# REUN_468349_001_PSU_Board_Button.net
KiCad netlist of a schematic drawn in Altium Designer
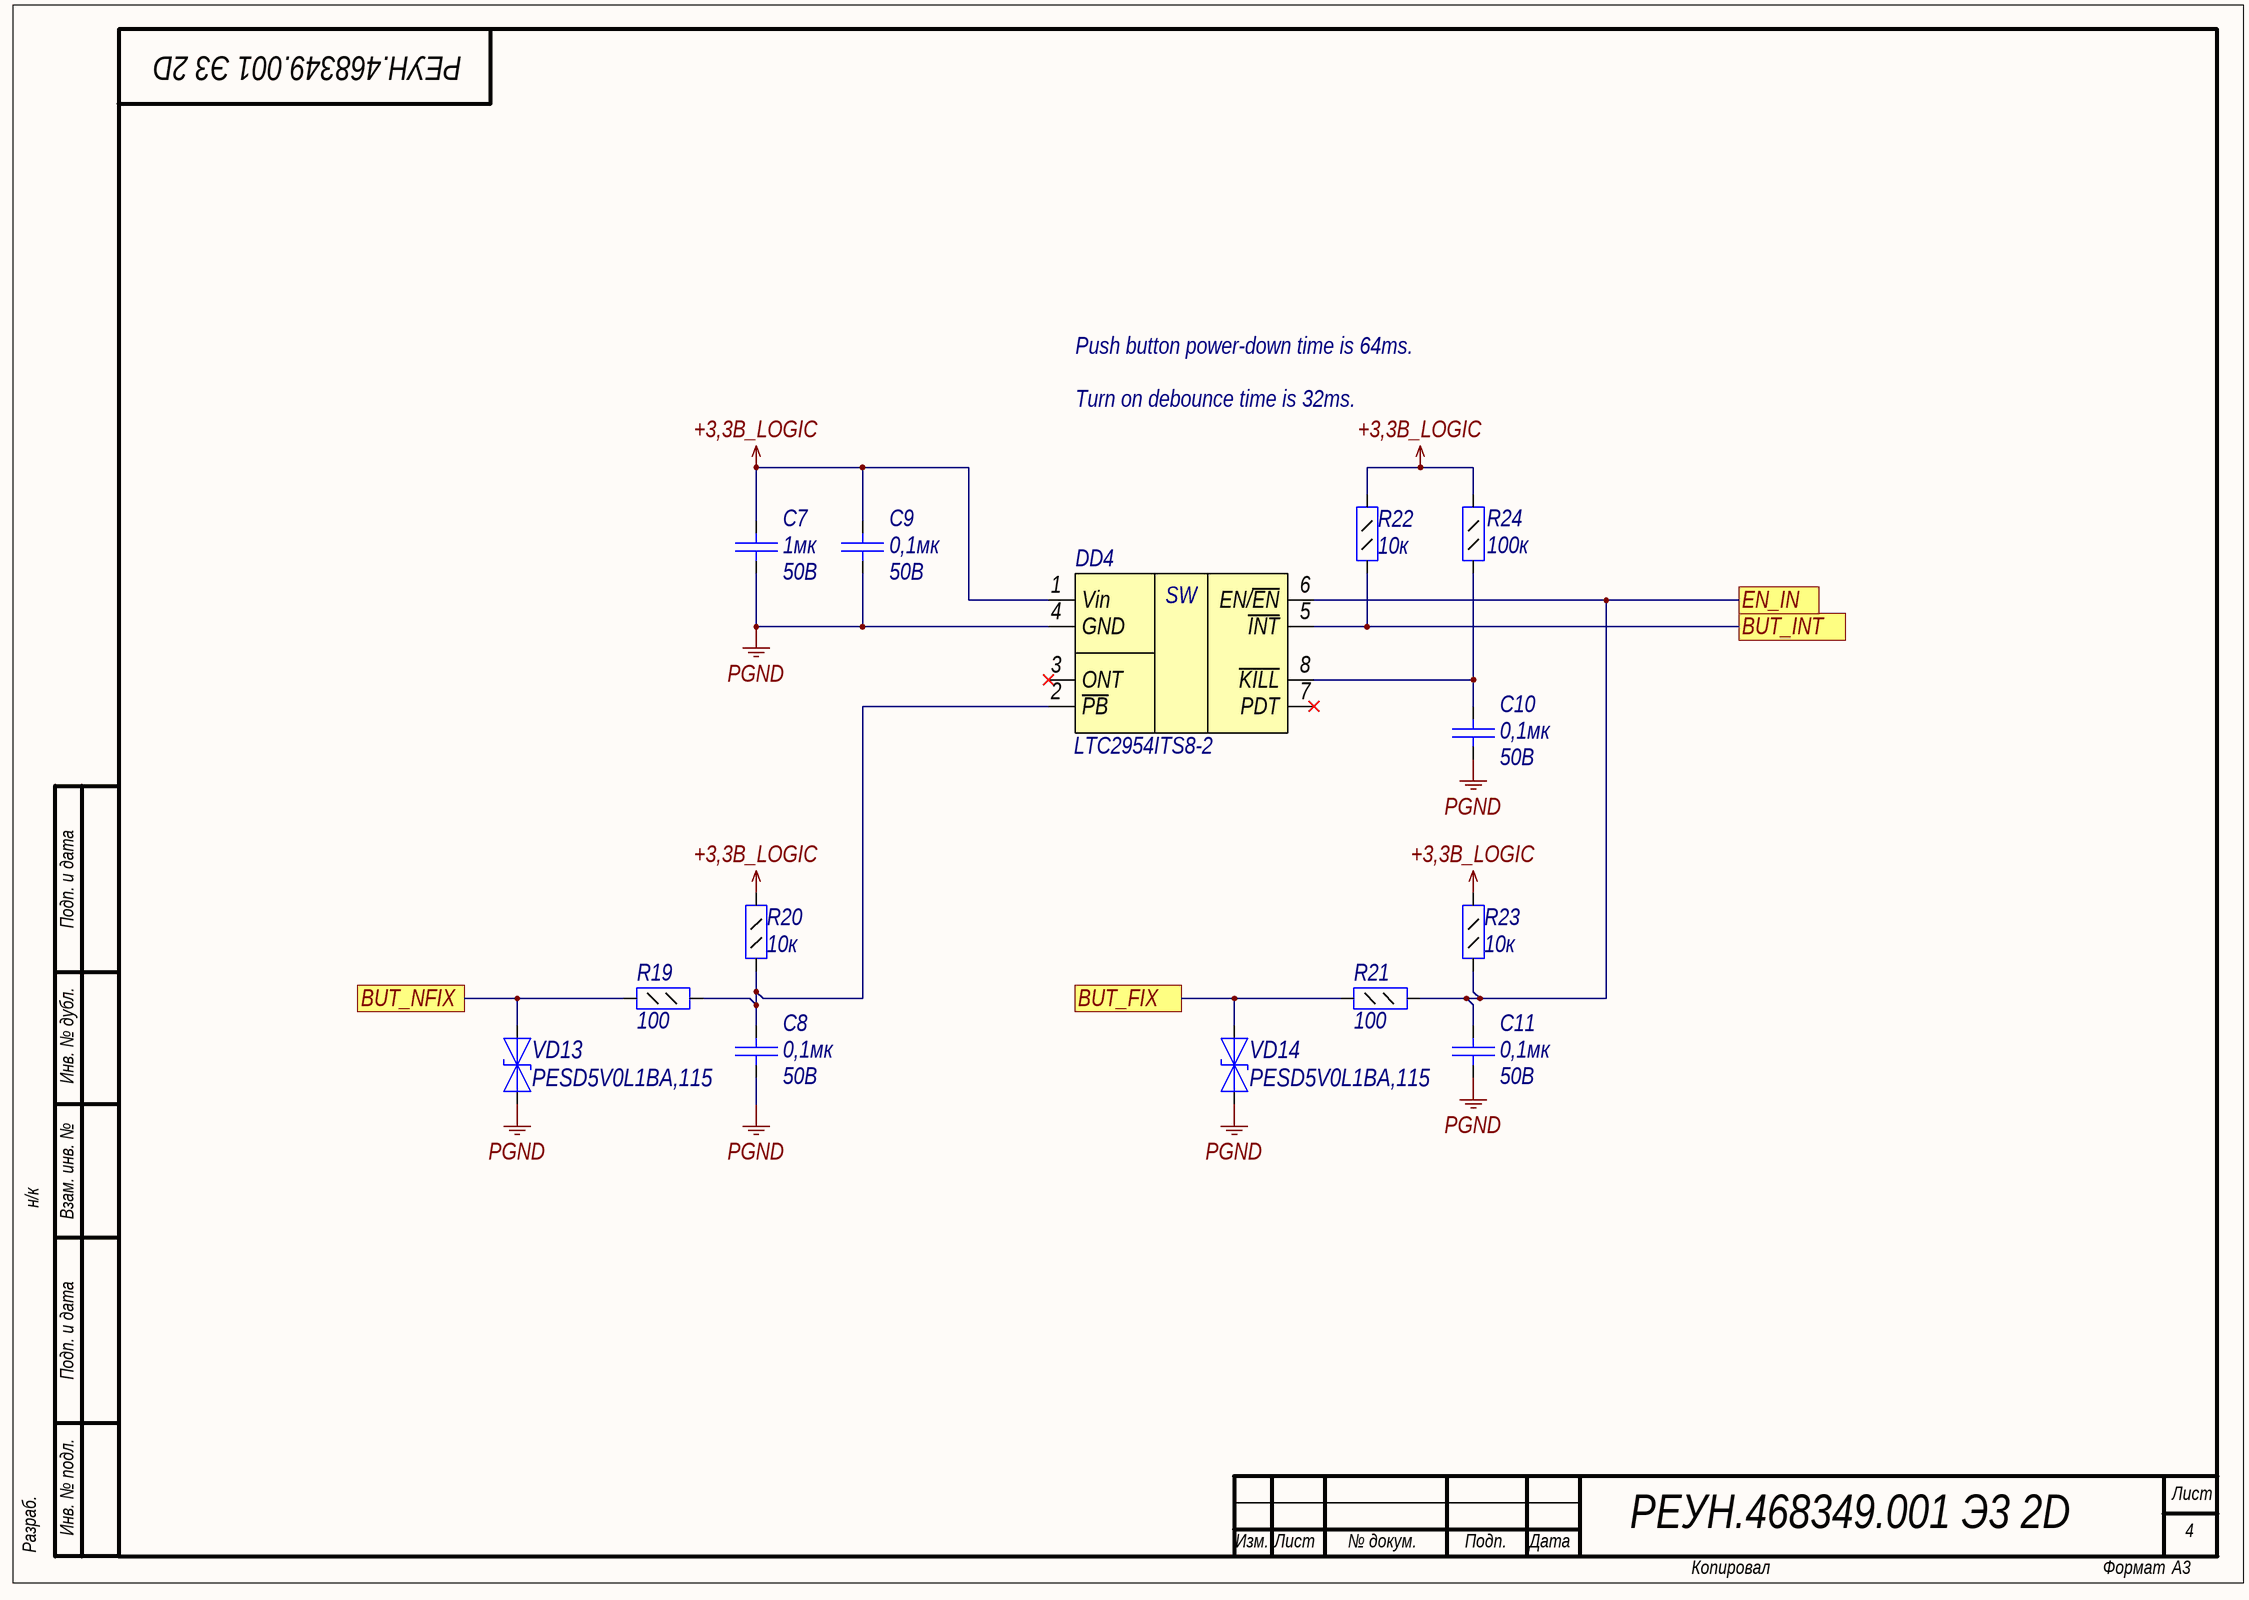
[diagram p0: REUN.468349.001_PSU_Board_Button.SchDoc]

(export (version "E")
  (design (tool "Eeschema 10.0.6"))
  (components
    (comp (ref "C7")
      (value "1мк")
      (footprint "C0805")
      (description "Конденсатор")
      (fields (field (name "VOLTAGE") "50B") (field (name "PART NUMBER") "GRM21BR71H105KA12L"))
      (libsource (lib "MOP44") (part "Capacitor"))
    )
    (comp (ref "C8")
      (value "0,1мк")
      (footprint "C0805")
      (description "Конденсатор")
      (fields (field (name "VOLTAGE") "50B") (field (name "PART NUMBER") "GRM21BR71H104KA01K"))
      (libsource (lib "MOP44") (part "Capacitor"))
    )
    (comp (ref "C9")
      (value "0,1мк")
      (footprint "C0805")
      (description "Конденсатор")
      (fields (field (name "VOLTAGE") "50B") (field (name "PART NUMBER") "GRM21BR71H104KA01K"))
      (libsource (lib "MOP44") (part "Capacitor"))
    )
    (comp (ref "C10")
      (value "0,1мк")
      (footprint "C0805")
      (description "Конденсатор")
      (fields (field (name "VOLTAGE") "50B") (field (name "PART NUMBER") "GRM21BR71H104KA01K"))
      (libsource (lib "MOP44") (part "Capacitor"))
    )
    (comp (ref "C11")
      (value "0,1мк")
      (footprint "C0805")
      (description "Конденсатор")
      (fields (field (name "VOLTAGE") "50B") (field (name "PART NUMBER") "GRM21BR71H104KA01K"))
      (libsource (lib "MOP44") (part "Capacitor"))
    )
    (comp (ref "DD4")
      (value "LTC2954ITS8-2")
      (footprint "SOT-23-8")
      (description "Pushbutton On/Off Controller with µP Interrupt")
      (libsource (lib "MOP44") (part "LTC2954"))
    )
    (comp (ref "R19")
      (value "100")
      (footprint "R0805")
      (description "Резистор")
      (fields (field (name "PART NUMBER") "RC0805FR-07100RL") (field (name "POWER") "0,125Вт"))
      (libsource (lib "REUN.468349.001_PSU_Board") (part "res49"))
    )
    (comp (ref "R20")
      (value "10к")
      (footprint "R0805")
      (description "Резистор")
      (fields (field (name "PART NUMBER") "RC0805FR-0710KL") (field (name "POWER") "0,125Вт"))
      (libsource (lib "MOP44") (part "Resistor_0,125Вт"))
    )
    (comp (ref "R21")
      (value "100")
      (footprint "R0805")
      (description "Резистор")
      (fields (field (name "PART NUMBER") "RC0805FR-07100RL") (field (name "POWER") "0,125Вт"))
      (libsource (lib "") (part "Resistor_0,125Вт_1"))
    )
    (comp (ref "R22")
      (value "10к")
      (footprint "R0805")
      (description "Резистор")
      (fields (field (name "PART NUMBER") "RC0805FR-0710KL") (field (name "POWER") "0,125Вт"))
      (libsource (lib "MOP44") (part "Resistor_0,125Вт"))
    )
    (comp (ref "R23")
      (value "10к")
      (footprint "R0805")
      (description "Резистор")
      (fields (field (name "PART NUMBER") "RC0805FR-0710KL") (field (name "POWER") "0,125Вт"))
      (libsource (lib "MOP44") (part "Resistor_0,125Вт"))
    )
    (comp (ref "R24")
      (value "100к")
      (footprint "R0805")
      (description "Резистор")
      (fields (field (name "PART NUMBER") "RC0805FR-07100KL") (field (name "POWER") "0,125Вт"))
      (libsource (lib "MOP44") (part "Resistor_0,125Вт"))
    )
    (comp (ref "VD13")
      (value "PESD5V0L1BA,115")
      (footprint "SOD-323")
      (description "Cтабилитрон (диод выпрямительный лавинный) двусторонний")
      (libsource (lib "MOP44") (part "DiodeZenerDual"))
    )
    (comp (ref "VD14")
      (value "PESD5V0L1BA,115")
      (footprint "SOD-323")
      (description "Cтабилитрон (диод выпрямительный лавинный) двусторонний")
      (libsource (lib "MOP44") (part "DiodeZenerDual"))
    )
  )
  (nets
    (net (code "1") (name "+3,3B_LOGIC") (class "Default")
      (node (ref "C7") (pin "2") (pinfunction "2_2") (pintype "passive"))
      (node (ref "C9") (pin "2") (pinfunction "2_2") (pintype "passive"))
      (node (ref "DD4") (pin "1") (pinfunction "Vin_1") (pintype "passive"))
      (node (ref "R20") (pin "2") (pinfunction "2_2") (pintype "passive"))
      (node (ref "R22") (pin "2") (pinfunction "2_2") (pintype "passive"))
      (node (ref "R23") (pin "2") (pinfunction "2_2") (pintype "passive"))
      (node (ref "R24") (pin "2") (pinfunction "2_2") (pintype "passive"))
    )
    (net (code "2") (name "/BUT_FIX") (class "Default")
      (node (ref "R21") (pin "1") (pinfunction "1_1") (pintype "passive"))
      (node (ref "VD14") (pin "1") (pinfunction "K_1") (pintype "passive"))
    )
    (net (code "3") (name "/BUT_INT") (class "Default")
      (node (ref "DD4") (pin "5") (pinfunction "~{INT}_5") (pintype "passive"))
      (node (ref "R22") (pin "1") (pinfunction "1_1") (pintype "passive"))
    )
    (net (code "4") (name "/BUT_NFIX") (class "Default")
      (node (ref "R19") (pin "1") (pinfunction "1_1") (pintype "passive"))
      (node (ref "VD13") (pin "1") (pinfunction "K_1") (pintype "passive"))
    )
    (net (code "5") (name "/EN_IN") (class "Default")
      (node (ref "C11") (pin "2") (pinfunction "2_2") (pintype "passive"))
      (node (ref "DD4") (pin "6") (pinfunction "EN/~{EN}_6") (pintype "passive"))
      (node (ref "R21") (pin "2") (pinfunction "2_2") (pintype "passive"))
      (node (ref "R23") (pin "1") (pinfunction "1_1") (pintype "passive"))
    )
    (net (code "6") (name "Net-(DD4-~{KILL})") (class "Default")
      (node (ref "C10") (pin "2") (pinfunction "2_2") (pintype "passive"))
      (node (ref "DD4") (pin "8") (pinfunction "~{KILL}_8") (pintype "passive"))
      (node (ref "R24") (pin "1") (pinfunction "1_1") (pintype "passive"))
    )
    (net (code "7") (name "Net-(DD4-~{PB})") (class "Default")
      (node (ref "C8") (pin "2") (pinfunction "2_2") (pintype "passive"))
      (node (ref "DD4") (pin "2") (pinfunction "~{PB}_2") (pintype "passive"))
      (node (ref "R19") (pin "2") (pinfunction "2_2") (pintype "passive"))
      (node (ref "R20") (pin "1") (pinfunction "1_1") (pintype "passive"))
    )
    (net (code "8") (name "PGND") (class "Default")
      (node (ref "C10") (pin "1") (pinfunction "1_1") (pintype "passive"))
      (node (ref "C11") (pin "1") (pinfunction "1_1") (pintype "passive"))
      (node (ref "C7") (pin "1") (pinfunction "1_1") (pintype "passive"))
      (node (ref "C8") (pin "1") (pinfunction "1_1") (pintype "passive"))
      (node (ref "C9") (pin "1") (pinfunction "1_1") (pintype "passive"))
      (node (ref "DD4") (pin "4") (pinfunction "GND_4") (pintype "passive"))
      (node (ref "VD13") (pin "2") (pinfunction "A_2") (pintype "passive"))
      (node (ref "VD14") (pin "2") (pinfunction "A_2") (pintype "passive"))
    )
    (net (code "9") (name "unconnected-(DD4-ONT-Pad3)") (class "Default")
      (node (ref "DD4") (pin "3") (pinfunction "ONT_3") (pintype "passive+no_connect"))
    )
    (net (code "10") (name "unconnected-(DD4-PDT-Pad7)") (class "Default")
      (node (ref "DD4") (pin "7") (pinfunction "PDT_7") (pintype "passive+no_connect"))
    )
  )
)
